# Sheet_Power.net
KiCad netlist of a schematic drawn in Altium Designer
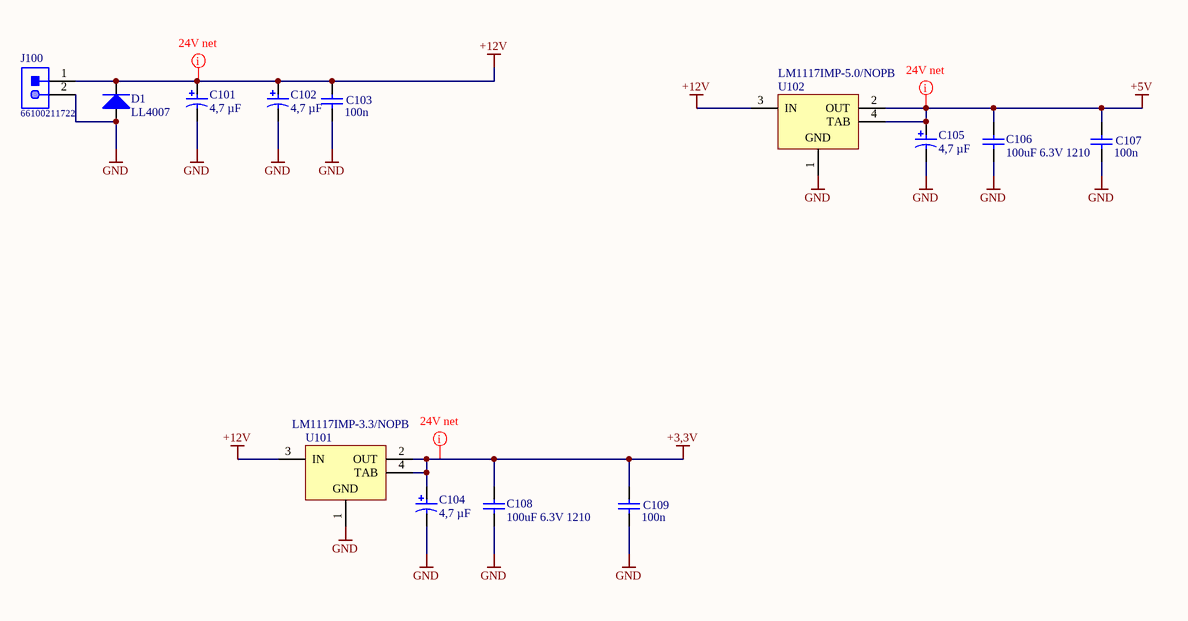
[diagram p0: Sheet_Power.SchDoc]

(export (version "E")
  (design (tool "Eeschema 10.0.6"))
  (components
    (comp (ref "C101")
      (value "4,7 µF")
      (footprint "A Package")
      (description "4,7 µF; 6V; Gr. A; T491A475K006AT")
      (fields (field (name "MANUFACTURER") "KEMET") (field (name "TOLERANCE") "±10%"))
      (libsource (lib "Altium Vault EMBL") (part "CMP-001-0039-3"))
    )
    (comp (ref "C102")
      (value "4,7 µF")
      (footprint "A Package")
      (description "4,7 µF; 6V; Gr. A; T491A475K006AT")
      (fields (field (name "MANUFACTURER") "KEMET") (field (name "TOLERANCE") "±10%"))
      (libsource (lib "Altium Vault EMBL") (part "CMP-001-0039-3"))
    )
    (comp (ref "C103")
      (value "100n")
      (footprint "CAPC2013X88X50ML20T25")
      (description "generic 0805 COG oder X7R Vielschichtkondensatoren max. +/-10%")
      (libsource (lib "Altium Vault EMBL") (part "CMP-001-0082-2"))
    )
    (comp (ref "C104")
      (value "4,7 µF")
      (footprint "A Package")
      (description "4,7 µF; 6V; Gr. A; T491A475K006AT")
      (fields (field (name "MANUFACTURER") "KEMET") (field (name "TOLERANCE") "±10%"))
      (libsource (lib "Altium Vault EMBL") (part "CMP-001-0039-3"))
    )
    (comp (ref "C105")
      (value "4,7 µF")
      (footprint "A Package")
      (description "4,7 µF; 6V; Gr. A; T491A475K006AT")
      (fields (field (name "MANUFACTURER") "KEMET") (field (name "TOLERANCE") "±10%"))
      (libsource (lib "Altium Vault EMBL") (part "CMP-001-0039-3"))
    )
    (comp (ref "C106")
      (value "100uF 6.3V 1210")
      (footprint "885012109004-Footprint-1")
      (description "Ceramic Capacitor, Ceramic, 100uF, 6.3V")
      (fields (field (name "PARTNUMBER") "885012109004"))
      (libsource (lib "EMBL") (part "CAP-NP-2"))
    )
    (comp (ref "C107")
      (value "100n")
      (footprint "CAPC2013X88X50ML20T25")
      (description "generic 0805 COG oder X7R Vielschichtkondensatoren max. +/-10%")
      (libsource (lib "Altium Vault EMBL") (part "CMP-001-0082-2"))
    )
    (comp (ref "C108")
      (value "100uF 6.3V 1210")
      (footprint "885012109004-Footprint-1")
      (description "Ceramic Capacitor, Ceramic, 100uF, 6.3V")
      (fields (field (name "PARTNUMBER") "885012109004"))
      (libsource (lib "EMBL") (part "CAP-NP-2"))
    )
    (comp (ref "C109")
      (value "100n")
      (footprint "CAPC2013X88X50ML20T25")
      (description "generic 0805 COG oder X7R Vielschichtkondensatoren max. +/-10%")
      (libsource (lib "Altium Vault EMBL") (part "CMP-001-0082-2"))
    )
    (comp (ref "D1")
      (value "LL4007")
      (footprint "LL4007")
      (description "LL4007;  Vf 1,1V @ 1A, If = 1A")
      (fields (field (name "MANUFACTURER") "TAIWAN SEMICONDUCTOR") (field (name "PARTNUMBER") "LL4007G L2"))
      (libsource (lib "Altium Vault EMBL") (part "CMP-001-0049-2"))
    )
    (comp (ref "J100")
      (value "66100211722")
      (footprint "66100211722")
      (description "Intercom Male Shrouded Locking Header WR-WTB, THT, Right Angled, pitch 2.54 mm, 1 x 2 position")
      (fields (field (name "MANUFACTURER") "Wurth Elektronik") (field (name "PUBLISHER") "WurthElektronik"))
      (libsource (lib "Altium Vault EMBL 3") (part "CMP-00524-A.1"))
    )
    (comp (ref "U101")
      (value "LM1117IMP-3.3/NOPB")
      (footprint "DCY0004A_N")
      (description "800mA Low-Dropout Linear Regulator, 4-pin SOT-223, Pb-Free")
      (fields (field (name "MANUFACTURER") "Texas Instruments"))
      (libsource (lib "Altium Vault EMBL") (part "CMP-00484-1"))
    )
    (comp (ref "U102")
      (value "LM1117IMP-5.0/NOPB")
      (footprint "DCY0004A_M")
      (description "800mA Low-Dropout Linear Regulator, 4-pin SOT-223, Pb-Free")
      (fields (field (name "MANUFACTURER") "Texas Instruments"))
      (libsource (lib "Altium Vault EMBL") (part "CMP-00485-1"))
    )
  )
  (nets
    (net (code "1") (name "+3,3V") (class "Default")
      (node (ref "C104") (pin "1") (pinfunction "1_1") (pintype "passive"))
      (node (ref "C108") (pin "2") (pinfunction "2_2") (pintype "passive"))
      (node (ref "C109") (pin "2") (pinfunction "2_2") (pintype "passive"))
      (node (ref "U101") (pin "2") (pinfunction "OUT_2") (pintype "power_in"))
      (node (ref "U101") (pin "4") (pinfunction "TAB_4") (pintype "power_in"))
    )
    (net (code "2") (name "+5V") (class "Default")
      (node (ref "C105") (pin "1") (pinfunction "1_1") (pintype "passive"))
      (node (ref "C106") (pin "2") (pinfunction "2_2") (pintype "passive"))
      (node (ref "C107") (pin "2") (pinfunction "2_2") (pintype "passive"))
      (node (ref "U102") (pin "2") (pinfunction "OUT_2") (pintype "power_in"))
      (node (ref "U102") (pin "4") (pinfunction "TAB_4") (pintype "power_in"))
    )
    (net (code "3") (name "+12V") (class "Default")
      (node (ref "C101") (pin "1") (pinfunction "1_1") (pintype "passive"))
      (node (ref "C102") (pin "1") (pinfunction "1_1") (pintype "passive"))
      (node (ref "C103") (pin "2") (pinfunction "2_2") (pintype "passive"))
      (node (ref "D1") (pin "2") (pinfunction "K_2") (pintype "passive"))
      (node (ref "J100") (pin "1") (pinfunction "1_1") (pintype "passive"))
      (node (ref "U101") (pin "3") (pinfunction "IN_3") (pintype "power_in"))
      (node (ref "U102") (pin "3") (pinfunction "IN_3") (pintype "power_in"))
    )
    (net (code "4") (name "GND") (class "Default")
      (node (ref "C101") (pin "2") (pinfunction "2_2") (pintype "passive"))
      (node (ref "C102") (pin "2") (pinfunction "2_2") (pintype "passive"))
      (node (ref "C103") (pin "1") (pinfunction "1_1") (pintype "passive"))
      (node (ref "C104") (pin "2") (pinfunction "2_2") (pintype "passive"))
      (node (ref "C105") (pin "2") (pinfunction "2_2") (pintype "passive"))
      (node (ref "C106") (pin "1") (pinfunction "1_1") (pintype "passive"))
      (node (ref "C107") (pin "1") (pinfunction "1_1") (pintype "passive"))
      (node (ref "C108") (pin "1") (pinfunction "1_1") (pintype "passive"))
      (node (ref "C109") (pin "1") (pinfunction "1_1") (pintype "passive"))
      (node (ref "D1") (pin "1") (pinfunction "A_1") (pintype "passive"))
      (node (ref "J100") (pin "2") (pinfunction "2_2") (pintype "passive"))
      (node (ref "U101") (pin "1") (pinfunction "GND_1") (pintype "power_in"))
      (node (ref "U102") (pin "1") (pinfunction "GND_1") (pintype "power_in"))
    )
  )
)
